# HI_Amplifer_schematic.net
KiCad netlist of a schematic drawn in Altium Designer
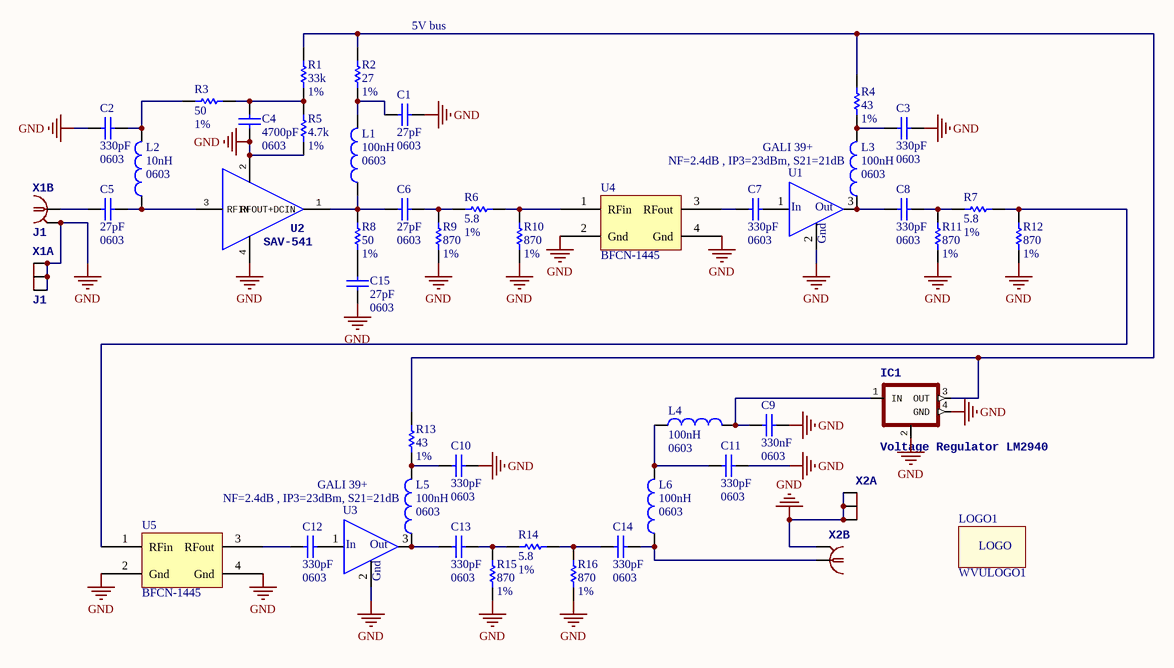
[diagram p0: HI_Amplifer_schematic.SchDoc]

(export (version "E")
  (design (tool "Eeschema 10.0.6"))
  (components
    (comp (ref "C1")
      (value "27pF")
      (footprint "0603")
      (description "Capacitor, Ceramic, 0603")
      (libsource (lib "HI_lib") (part "Cap0603"))
    )
    (comp (ref "C2")
      (value "330pF")
      (footprint "0603")
      (description "Capacitor, Ceramic, 0603")
      (libsource (lib "HI_lib") (part "Cap0603"))
    )
    (comp (ref "C3")
      (value "330pF")
      (footprint "0603")
      (description "Capacitor, Ceramic, 0603")
      (libsource (lib "HI_lib") (part "Cap0603"))
    )
    (comp (ref "C4")
      (value "4700pF")
      (footprint "0603")
      (description "Capacitor, Ceramic, 0603")
      (libsource (lib "HI_lib") (part "Cap0603"))
    )
    (comp (ref "C5")
      (value "27pF")
      (footprint "0603")
      (description "Capacitor, Ceramic, 0603")
      (libsource (lib "HI_lib") (part "Cap0603"))
    )
    (comp (ref "C6")
      (value "27pF")
      (footprint "0603")
      (description "Capacitor, Ceramic, 0603")
      (libsource (lib "HI_lib") (part "Cap0603"))
    )
    (comp (ref "C7")
      (value "330pF")
      (footprint "0603")
      (description "Capacitor, Ceramic, 0603")
      (libsource (lib "HI_lib") (part "Cap0603"))
    )
    (comp (ref "C8")
      (value "330pF")
      (footprint "0603")
      (description "Capacitor, Ceramic, 0603")
      (libsource (lib "HI_lib") (part "Cap0603"))
    )
    (comp (ref "C9")
      (value "330nF")
      (footprint "0603")
      (description "Capacitor, Ceramic, 0603")
      (libsource (lib "HI_lib") (part "Cap0603"))
    )
    (comp (ref "C10")
      (value "330pF")
      (footprint "0603")
      (description "Capacitor, Ceramic, 0603")
      (libsource (lib "HI_lib") (part "Cap0603"))
    )
    (comp (ref "C11")
      (value "330pF")
      (footprint "0603")
      (description "Capacitor, Ceramic, 0603")
      (libsource (lib "HI_lib") (part "Cap0603"))
    )
    (comp (ref "C12")
      (value "330pF")
      (footprint "0603")
      (description "Capacitor, Ceramic, 0603")
      (libsource (lib "HI_lib") (part "Cap0603"))
    )
    (comp (ref "C13")
      (value "330pF")
      (footprint "0603")
      (description "Capacitor, Ceramic, 0603")
      (libsource (lib "HI_lib") (part "Cap0603"))
    )
    (comp (ref "C14")
      (value "330pF")
      (footprint "0603")
      (description "Capacitor, Ceramic, 0603")
      (libsource (lib "HI_lib") (part "Cap0603"))
    )
    (comp (ref "C15")
      (value "27pF")
      (footprint "0603")
      (description "Capacitor, Ceramic, 0603")
      (libsource (lib "HI_lib") (part "Cap0603"))
    )
    (comp (ref "IC1")
      (value "Voltage Regulator LM2940")
      (footprint "SOT223")
      (libsource (lib "HI_lib") (part "V_REG_LM2940SOT223_1"))
    )
    (comp (ref "L1")
      (value "100nH")
      (footprint "0805")
      (description "Inductor")
      (fields (field (name "MANUFACTURER") "Taiyo Yuden") (field (name "PARAM") "0603"))
      (libsource (lib "HI_lib") (part "Inductor0"))
    )
    (comp (ref "L2")
      (value "10nH")
      (footprint "0805")
      (description "Inductor")
      (fields (field (name "MANUFACTURER") "Taiyo Yuden") (field (name "PARAM") "0603"))
      (libsource (lib "HI_lib") (part "Inductor0"))
    )
    (comp (ref "L3")
      (value "100nH")
      (footprint "0805")
      (description "Inductor")
      (fields (field (name "MANUFACTURER") "Taiyo Yuden") (field (name "PARAM") "0603"))
      (libsource (lib "HI_lib") (part "Inductor0"))
    )
    (comp (ref "L4")
      (value "100nH")
      (footprint "0805")
      (description "Inductor")
      (fields (field (name "MANUFACTURER") "Taiyo Yuden") (field (name "PARAM") "0603"))
      (libsource (lib "HI_lib") (part "Inductor0"))
    )
    (comp (ref "L5")
      (value "100nH")
      (footprint "0805")
      (description "Inductor")
      (fields (field (name "MANUFACTURER") "Taiyo Yuden") (field (name "PARAM") "0603"))
      (libsource (lib "HI_lib") (part "Inductor0"))
    )
    (comp (ref "L6")
      (value "100nH")
      (footprint "0805")
      (description "Inductor")
      (fields (field (name "MANUFACTURER") "Taiyo Yuden") (field (name "PARAM") "0603"))
      (libsource (lib "HI_lib") (part "Inductor0"))
    )
    (comp (ref "LOGO1")
      (value "WVULOGO1")
      (footprint "WVULOGO1")
      (libsource (lib "HI_lib") (part "WVULOGO1"))
    )
    (comp (ref "R1")
      (value "33k")
      (footprint "0603")
      (description "Resistor")
      (fields (field (name "PARAM") "1%"))
      (libsource (lib "HI_lib") (part "Res0603"))
    )
    (comp (ref "R2")
      (value "27")
      (footprint "0603")
      (description "Resistor")
      (fields (field (name "PARAM") "1%"))
      (libsource (lib "HI_lib") (part "Res0603"))
    )
    (comp (ref "R3")
      (value "50")
      (footprint "0603")
      (description "Resistor")
      (fields (field (name "PARAM") "1%"))
      (libsource (lib "HI_lib") (part "Res0603"))
    )
    (comp (ref "R4")
      (value "43")
      (footprint "0603")
      (description "Resistor")
      (fields (field (name "PARAM") "1%"))
      (libsource (lib "HI_lib") (part "Res0603"))
    )
    (comp (ref "R5")
      (value "4.7k")
      (footprint "0603")
      (description "Resistor")
      (fields (field (name "PARAM") "1%"))
      (libsource (lib "HI_lib") (part "Res0603"))
    )
    (comp (ref "R6")
      (value "5.8")
      (footprint "0603")
      (description "Resistor")
      (fields (field (name "PARAM") "1%"))
      (libsource (lib "HI_lib") (part "Res0603"))
    )
    (comp (ref "R7")
      (value "5.8")
      (footprint "0603")
      (description "Resistor")
      (fields (field (name "PARAM") "1%"))
      (libsource (lib "HI_lib") (part "Res0603"))
    )
    (comp (ref "R8")
      (value "50")
      (footprint "0603")
      (description "Resistor")
      (fields (field (name "PARAM") "1%"))
      (libsource (lib "HI_lib") (part "Res0603"))
    )
    (comp (ref "R9")
      (value "870")
      (footprint "0603")
      (description "Resistor")
      (fields (field (name "PARAM") "1%"))
      (libsource (lib "HI_lib") (part "Res0603"))
    )
    (comp (ref "R10")
      (value "870")
      (footprint "0603")
      (description "Resistor")
      (fields (field (name "PARAM") "1%"))
      (libsource (lib "HI_lib") (part "Res0603"))
    )
    (comp (ref "R11")
      (value "870")
      (footprint "0603")
      (description "Resistor")
      (fields (field (name "PARAM") "1%"))
      (libsource (lib "HI_lib") (part "Res0603"))
    )
    (comp (ref "R12")
      (value "870")
      (footprint "0603")
      (description "Resistor")
      (fields (field (name "PARAM") "1%"))
      (libsource (lib "HI_lib") (part "Res0603"))
    )
    (comp (ref "R13")
      (value "43")
      (footprint "0603")
      (description "Resistor")
      (fields (field (name "PARAM") "1%"))
      (libsource (lib "HI_lib") (part "Res0603"))
    )
    (comp (ref "R14")
      (value "5.8")
      (footprint "0603")
      (description "Resistor")
      (fields (field (name "PARAM") "1%"))
      (libsource (lib "HI_lib") (part "Res0603"))
    )
    (comp (ref "R15")
      (value "870")
      (footprint "0603")
      (description "Resistor")
      (fields (field (name "PARAM") "1%"))
      (libsource (lib "HI_lib") (part "Res0603"))
    )
    (comp (ref "R16")
      (value "870")
      (footprint "0603")
      (description "Resistor")
      (fields (field (name "PARAM") "1%"))
      (libsource (lib "HI_lib") (part "Res0603"))
    )
    (comp (ref "U1")
      (value "GALI 39+")
      (footprint "SBA5089")
      (description "RFMD Amplifier DC-5Ghz")
      (fields (field (name "PARTCONSTRAINTS") "NF=2.4dB , IP3=23dBm, S21=21dB"))
      (libsource (lib "HI_lib") (part "GALI 39+"))
    )
    (comp (ref "U2") (value "SAV-541") (footprint "SOT343") (libsource (lib "HI_lib") (part "SAV-541")))
    (comp (ref "U3")
      (value "GALI 39+")
      (footprint "SBA5089")
      (description "RFMD Amplifier DC-5Ghz")
      (fields (field (name "PARTCONSTRAINTS") "NF=2.4dB , IP3=23dBm, S21=21dB"))
      (libsource (lib "HI_lib") (part "GALI 39+"))
    )
    (comp (ref "U4")
      (value "BFCN-1445")
      (footprint "FV1206")
      (fields (field (name "MANUFACTURER") "Minicircuits"))
      (libsource (lib "HI_lib") (part "BFCN-1445"))
    )
    (comp (ref "U5")
      (value "BFCN-1445")
      (footprint "FV1206")
      (fields (field (name "MANUFACTURER") "Minicircuits"))
      (libsource (lib "HI_lib") (part "BFCN-1445"))
    )
    (comp (ref "X1") (value "J1") (footprint "LTI-SASF54GT") (libsource (lib "HI_lib") (part "LTI-SASF54GT")))
    (comp (ref "X2")
      (value "SMA vertical PCB thrue hole jack   Source: Lighthorse Technologies, inc. SASF54GT.pdf")
      (footprint "LTI-SASF54GT")
      (libsource (lib "HI_lib") (part "LTI-SASF54GT"))
    )
  )
  (nets
    (net (code "1") (name "GND") (class "Default")
      (node (ref "C1") (pin "2") (pinfunction "2_2") (pintype "passive"))
      (node (ref "C10") (pin "2") (pinfunction "2_2") (pintype "passive"))
      (node (ref "C11") (pin "2") (pinfunction "2_2") (pintype "passive"))
      (node (ref "C15") (pin "1") (pinfunction "1_1") (pintype "passive"))
      (node (ref "C2") (pin "1") (pinfunction "1_1") (pintype "passive"))
      (node (ref "C3") (pin "2") (pinfunction "2_2") (pintype "passive"))
      (node (ref "C4") (pin "1") (pinfunction "1_1") (pintype "passive"))
      (node (ref "C9") (pin "2") (pinfunction "2_2") (pintype "passive"))
      (node (ref "IC1") (pin "2") (pinfunction "GND_2") (pintype "passive"))
      (node (ref "IC1") (pin "4") (pinfunction "GND_4") (pintype "output"))
      (node (ref "R10") (pin "1") (pinfunction "1_1") (pintype "passive"))
      (node (ref "R11") (pin "1") (pinfunction "1_1") (pintype "passive"))
      (node (ref "R12") (pin "1") (pinfunction "1_1") (pintype "passive"))
      (node (ref "R15") (pin "1") (pinfunction "1_1") (pintype "passive"))
      (node (ref "R16") (pin "1") (pinfunction "1_1") (pintype "passive"))
      (node (ref "R5") (pin "1") (pinfunction "1_1") (pintype "passive"))
      (node (ref "R9") (pin "1") (pinfunction "1_1") (pintype "passive"))
      (node (ref "U1") (pin "2") (pinfunction "Gnd_2") (pintype "passive"))
      (node (ref "U2") (pin "2") (pinfunction "GND@2_2") (pintype "open_emitter"))
      (node (ref "U2") (pin "4") (pinfunction "GND@4_4") (pintype "open_emitter"))
      (node (ref "U3") (pin "2") (pinfunction "Gnd_2") (pintype "passive"))
      (node (ref "U4") (pin "2") (pinfunction "Gnd_2") (pintype "passive"))
      (node (ref "U4") (pin "4") (pinfunction "Gnd_4") (pintype "passive"))
      (node (ref "U5") (pin "2") (pinfunction "Gnd_2") (pintype "passive"))
      (node (ref "U5") (pin "4") (pinfunction "Gnd_4") (pintype "passive"))
      (node (ref "X1") (pin "2") (pinfunction "GND_2") (pintype "power_in"))
      (node (ref "X1") (pin "3") (pinfunction "GND@1_3") (pintype "power_in"))
      (node (ref "X1") (pin "4") (pinfunction "GND@2_4") (pintype "power_in"))
      (node (ref "X1") (pin "5") (pinfunction "GND@3_5") (pintype "power_in"))
      (node (ref "X2") (pin "2") (pinfunction "GND_2") (pintype "power_in"))
      (node (ref "X2") (pin "3") (pinfunction "GND@1_3") (pintype "power_in"))
      (node (ref "X2") (pin "4") (pinfunction "GND@2_4") (pintype "power_in"))
      (node (ref "X2") (pin "5") (pinfunction "GND@3_5") (pintype "power_in"))
    )
    (net (code "2") (name "Net-(C1-Pad1)") (class "Default")
      (node (ref "C1") (pin "1") (pinfunction "1_1") (pintype "passive"))
      (node (ref "L1") (pin "2") (pinfunction "2_2") (pintype "passive"))
      (node (ref "R2") (pin "1") (pinfunction "1_1") (pintype "passive"))
    )
    (net (code "3") (name "Net-(C2-Pad2)") (class "Default")
      (node (ref "C2") (pin "2") (pinfunction "2_2") (pintype "passive"))
      (node (ref "L2") (pin "2") (pinfunction "2_2") (pintype "passive"))
      (node (ref "R3") (pin "1") (pinfunction "1_1") (pintype "passive"))
    )
    (net (code "4") (name "Net-(C3-Pad1)") (class "Default")
      (node (ref "C3") (pin "1") (pinfunction "1_1") (pintype "passive"))
      (node (ref "L3") (pin "2") (pinfunction "2_2") (pintype "passive"))
      (node (ref "R4") (pin "1") (pinfunction "1_1") (pintype "passive"))
    )
    (net (code "5") (name "Net-(C4-Pad2)") (class "Default")
      (node (ref "C4") (pin "2") (pinfunction "2_2") (pintype "passive"))
      (node (ref "R1") (pin "1") (pinfunction "1_1") (pintype "passive"))
      (node (ref "R3") (pin "2") (pinfunction "2_2") (pintype "passive"))
      (node (ref "R5") (pin "2") (pinfunction "2_2") (pintype "passive"))
    )
    (net (code "6") (name "Net-(C5-Pad1)") (class "Default")
      (node (ref "C5") (pin "1") (pinfunction "1_1") (pintype "passive"))
      (node (ref "X1") (pin "1") (pinfunction "1_1") (pintype "passive"))
    )
    (net (code "7") (name "Net-(C6-Pad2)") (class "Default")
      (node (ref "C6") (pin "2") (pinfunction "2_2") (pintype "passive"))
      (node (ref "R6") (pin "1") (pinfunction "1_1") (pintype "passive"))
      (node (ref "R9") (pin "2") (pinfunction "2_2") (pintype "passive"))
    )
    (net (code "8") (name "Net-(C8-Pad2)") (class "Default")
      (node (ref "C8") (pin "2") (pinfunction "2_2") (pintype "passive"))
      (node (ref "R11") (pin "2") (pinfunction "2_2") (pintype "passive"))
      (node (ref "R7") (pin "1") (pinfunction "1_1") (pintype "passive"))
    )
    (net (code "9") (name "Net-(C10-Pad1)") (class "Default")
      (node (ref "C10") (pin "1") (pinfunction "1_1") (pintype "passive"))
      (node (ref "L5") (pin "2") (pinfunction "2_2") (pintype "passive"))
      (node (ref "R13") (pin "1") (pinfunction "1_1") (pintype "passive"))
    )
    (net (code "10") (name "Net-(C11-Pad1)") (class "Default")
      (node (ref "C11") (pin "1") (pinfunction "1_1") (pintype "passive"))
      (node (ref "L4") (pin "1") (pinfunction "1_1") (pintype "passive"))
      (node (ref "L6") (pin "2") (pinfunction "2_2") (pintype "passive"))
    )
    (net (code "11") (name "Net-(C13-Pad2)") (class "Default")
      (node (ref "C13") (pin "2") (pinfunction "2_2") (pintype "passive"))
      (node (ref "R14") (pin "1") (pinfunction "1_1") (pintype "passive"))
      (node (ref "R15") (pin "2") (pinfunction "2_2") (pintype "passive"))
    )
    (net (code "12") (name "Net-(C14-Pad1)") (class "Default")
      (node (ref "C14") (pin "1") (pinfunction "1_1") (pintype "passive"))
      (node (ref "R14") (pin "2") (pinfunction "2_2") (pintype "passive"))
      (node (ref "R16") (pin "2") (pinfunction "2_2") (pintype "passive"))
    )
    (net (code "13") (name "Net-(C14-Pad2)") (class "Default")
      (node (ref "C14") (pin "2") (pinfunction "2_2") (pintype "passive"))
      (node (ref "L6") (pin "1") (pinfunction "1_1") (pintype "passive"))
      (node (ref "X2") (pin "1") (pinfunction "1_1") (pintype "passive"))
    )
    (net (code "14") (name "Net-(C15-Pad2)") (class "Default")
      (node (ref "C15") (pin "2") (pinfunction "2_2") (pintype "passive"))
      (node (ref "R8") (pin "1") (pinfunction "1_1") (pintype "passive"))
    )
    (net (code "15") (name "Net-(IC1-IN)") (class "Default")
      (node (ref "C9") (pin "1") (pinfunction "1_1") (pintype "passive"))
      (node (ref "IC1") (pin "1") (pinfunction "IN_1") (pintype "passive"))
      (node (ref "L4") (pin "2") (pinfunction "2_2") (pintype "passive"))
    )
    (net (code "16") (name "Net-(IC1-OUT)") (class "Default")
      (node (ref "IC1") (pin "3") (pinfunction "OUT_3") (pintype "output"))
      (node (ref "R1") (pin "2") (pinfunction "2_2") (pintype "passive"))
      (node (ref "R13") (pin "2") (pinfunction "2_2") (pintype "passive"))
      (node (ref "R2") (pin "2") (pinfunction "2_2") (pintype "passive"))
      (node (ref "R4") (pin "2") (pinfunction "2_2") (pintype "passive"))
    )
    (net (code "17") (name "Net-(U1-In)") (class "Default")
      (node (ref "C7") (pin "2") (pinfunction "2_2") (pintype "passive"))
      (node (ref "U1") (pin "1") (pinfunction "In_1") (pintype "passive"))
    )
    (net (code "18") (name "Net-(U1-Out)") (class "Default")
      (node (ref "C8") (pin "1") (pinfunction "1_1") (pintype "passive"))
      (node (ref "L3") (pin "1") (pinfunction "1_1") (pintype "passive"))
      (node (ref "U1") (pin "3") (pinfunction "Out_3") (pintype "passive"))
    )
    (net (code "19") (name "Net-(U2-RFIN)") (class "Default")
      (node (ref "C5") (pin "2") (pinfunction "2_2") (pintype "passive"))
      (node (ref "L2") (pin "1") (pinfunction "1_1") (pintype "passive"))
      (node (ref "U2") (pin "3") (pinfunction "RFIN_3") (pintype "passive"))
    )
    (net (code "20") (name "Net-(U2-RFOUT+DCIN)") (class "Default")
      (node (ref "C6") (pin "1") (pinfunction "1_1") (pintype "passive"))
      (node (ref "L1") (pin "1") (pinfunction "1_1") (pintype "passive"))
      (node (ref "R8") (pin "2") (pinfunction "2_2") (pintype "passive"))
      (node (ref "U2") (pin "1") (pinfunction "RFOUT+DCIN_1") (pintype "passive"))
    )
    (net (code "21") (name "Net-(U3-In)") (class "Default")
      (node (ref "C12") (pin "2") (pinfunction "2_2") (pintype "passive"))
      (node (ref "U3") (pin "1") (pinfunction "In_1") (pintype "passive"))
    )
    (net (code "22") (name "Net-(U3-Out)") (class "Default")
      (node (ref "C13") (pin "1") (pinfunction "1_1") (pintype "passive"))
      (node (ref "L5") (pin "1") (pinfunction "1_1") (pintype "passive"))
      (node (ref "U3") (pin "3") (pinfunction "Out_3") (pintype "passive"))
    )
    (net (code "23") (name "Net-(U4-RFin)") (class "Default")
      (node (ref "R10") (pin "2") (pinfunction "2_2") (pintype "passive"))
      (node (ref "R6") (pin "2") (pinfunction "2_2") (pintype "passive"))
      (node (ref "U4") (pin "1") (pinfunction "RFin_1") (pintype "passive"))
    )
    (net (code "24") (name "Net-(U4-RFout)") (class "Default")
      (node (ref "C7") (pin "1") (pinfunction "1_1") (pintype "passive"))
      (node (ref "U4") (pin "3") (pinfunction "RFout_3") (pintype "passive"))
    )
    (net (code "25") (name "Net-(U5-RFin)") (class "Default")
      (node (ref "R12") (pin "2") (pinfunction "2_2") (pintype "passive"))
      (node (ref "R7") (pin "2") (pinfunction "2_2") (pintype "passive"))
      (node (ref "U5") (pin "1") (pinfunction "RFin_1") (pintype "passive"))
    )
    (net (code "26") (name "Net-(U5-RFout)") (class "Default")
      (node (ref "C12") (pin "1") (pinfunction "1_1") (pintype "passive"))
      (node (ref "U5") (pin "3") (pinfunction "RFout_3") (pintype "passive"))
    )
  )
)
